# Trigger_Sequencer_Arduino_board.net
KiCad netlist of a schematic drawn in EAGLE
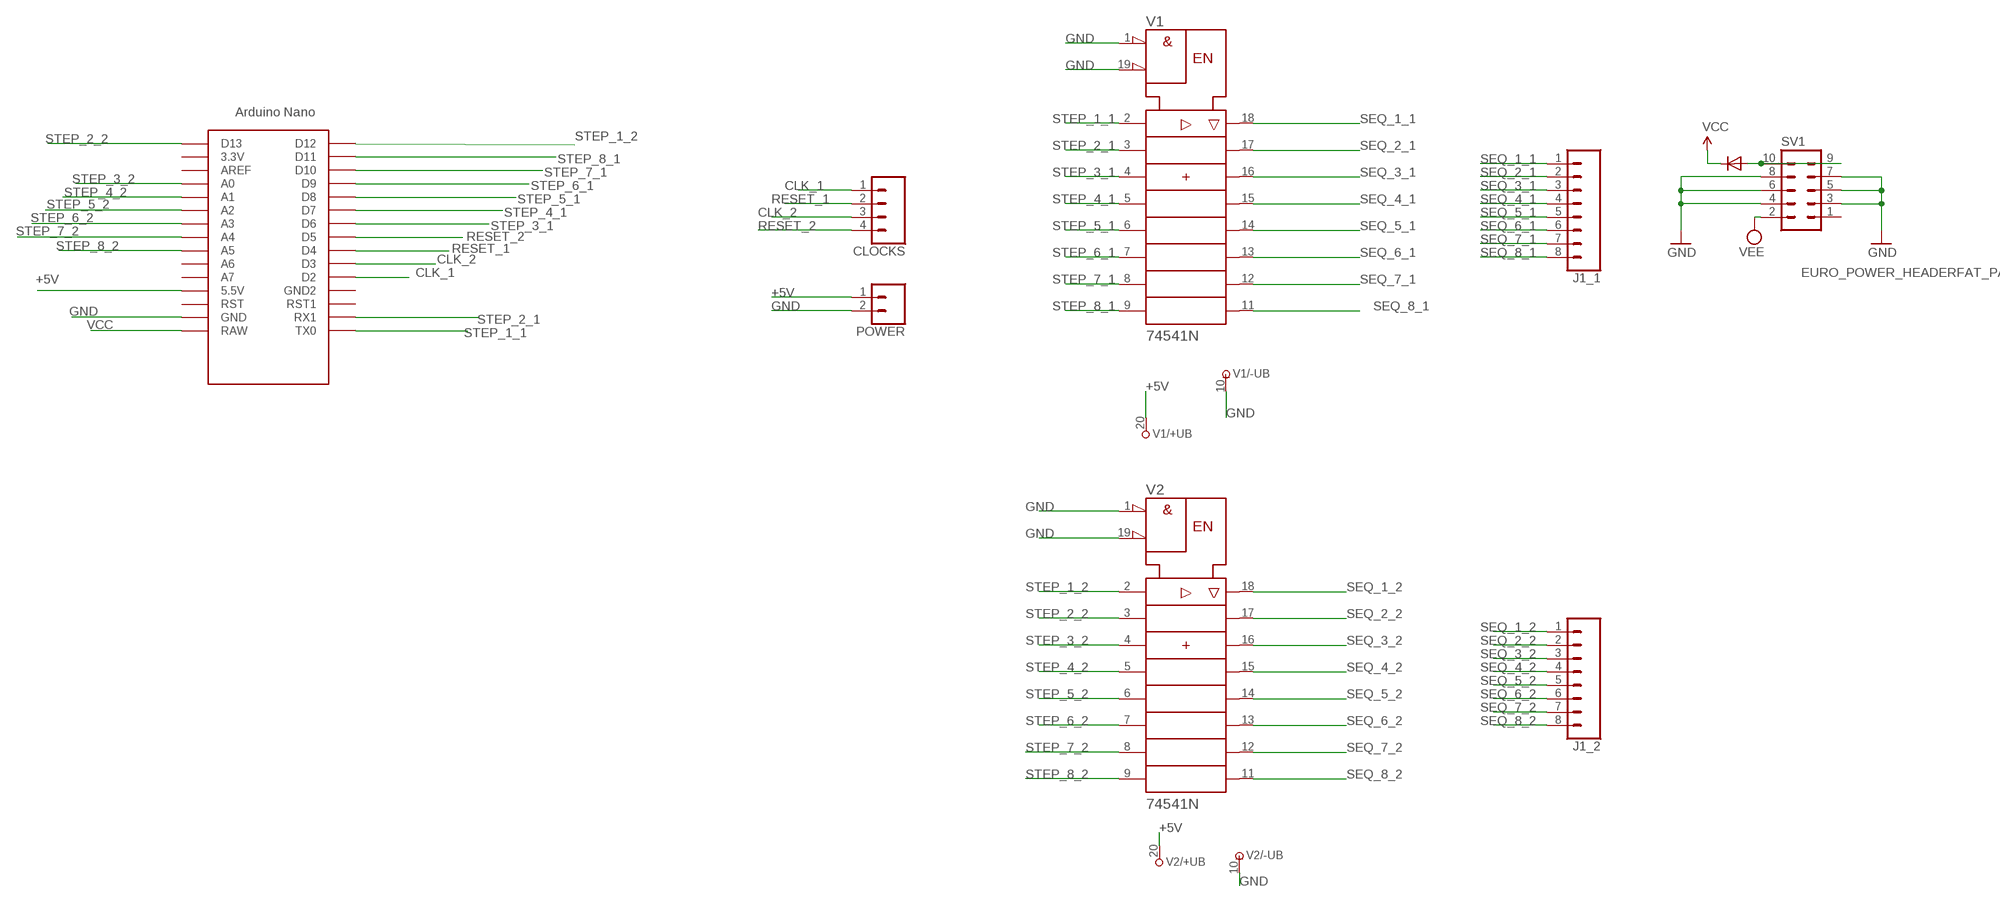
[diagram p0: schematic, sheet 1]

(export (version "E")
  (design (tool "Eeschema 10.0.6"))
  (components
    (comp (ref "CLOCKS")
      (value "CONN_04")
      (footprint "eagle-import:1X04")
      (libsource (lib "eagle-import") (part "CONN_04"))
    )
    (comp (ref "D2")
      (value "1N5819HW")
      (footprint "eagle-import:DO-1N4148")
      (libsource (lib "eagle-import") (part "DIODEDO-1N4148"))
    )
    (comp (ref "J1_1")
      (value "CONN_08NO_SILK_FEMALE_PTH")
      (footprint "eagle-import:1X08_NO_SILK")
      (libsource (lib "eagle-import") (part "CONN_08NO_SILK_FEMALE_PTH"))
    )
    (comp (ref "J1_2")
      (value "CONN_08NO_SILK_FEMALE_PTH")
      (footprint "eagle-import:1X08_NO_SILK")
      (libsource (lib "eagle-import") (part "CONN_08NO_SILK_FEMALE_PTH"))
    )
    (comp (ref "POWER")
      (value "CONN_02")
      (footprint "eagle-import:1X02")
      (libsource (lib "eagle-import") (part "CONN_02"))
    )
    (comp (ref "SV1")
      (value "EURO_POWER_HEADERFAT_PADS")
      (footprint "eagle-import:EURO_PWR_HEADER_FAT")
      (libsource (lib "eagle-import") (part "EURO_POWER_HEADERFAT_PADS"))
    )
    (comp (ref "U$1")
      (value "NANO")
      (footprint "eagle-import:NANO")
      (libsource (lib "eagle-import") (part "NANO"))
    )
    (comp (ref "V1")
      (value "74541N")
      (footprint "eagle-import:DIL20")
      (libsource (lib "eagle-import") (part "74541N"))
    )
    (comp (ref "V2")
      (value "74541N")
      (footprint "eagle-import:DIL20")
      (libsource (lib "eagle-import") (part "74541N"))
    )
  )
  (nets
    (net (code "1") (name "/+5V") (class "Default")
      (node (ref "POWER") (pin "1") (pinfunction "1_1") (pintype "passive"))
      (node (ref "U$1") (pin "5V") (pinfunction "5.5V_5V") (pintype "bidirectional"))
      (node (ref "V1") (pin "20") (pinfunction "+UB_20") (pintype "power_in"))
      (node (ref "V2") (pin "20") (pinfunction "+UB_20") (pintype "power_in"))
    )
    (net (code "2") (name "/CLK_1") (class "Default")
      (node (ref "CLOCKS") (pin "1") (pinfunction "1_1") (pintype "passive"))
      (node (ref "U$1") (pin "D2") (pinfunction "D2_D2") (pintype "bidirectional"))
    )
    (net (code "3") (name "/CLK_2") (class "Default")
      (node (ref "CLOCKS") (pin "3") (pinfunction "3_3") (pintype "passive"))
      (node (ref "U$1") (pin "D3") (pinfunction "D3_D3") (pintype "bidirectional"))
    )
    (net (code "4") (name "/RESET_1") (class "Default")
      (node (ref "CLOCKS") (pin "2") (pinfunction "2_2") (pintype "passive"))
      (node (ref "U$1") (pin "D4") (pinfunction "D4_D4") (pintype "bidirectional"))
    )
    (net (code "5") (name "/RESET_2") (class "Default")
      (node (ref "CLOCKS") (pin "4") (pinfunction "4_4") (pintype "passive"))
      (node (ref "U$1") (pin "D5") (pinfunction "D5_D5") (pintype "bidirectional"))
    )
    (net (code "6") (name "/SEQ_1_1") (class "Default")
      (node (ref "J1_1") (pin "1") (pinfunction "1_1") (pintype "passive"))
      (node (ref "V1") (pin "18") (pinfunction "Y1_18") (pintype "tri_state"))
    )
    (net (code "7") (name "/SEQ_1_2") (class "Default")
      (node (ref "J1_2") (pin "1") (pinfunction "1_1") (pintype "passive"))
      (node (ref "V2") (pin "18") (pinfunction "Y1_18") (pintype "tri_state"))
    )
    (net (code "8") (name "/SEQ_2_1") (class "Default")
      (node (ref "J1_1") (pin "2") (pinfunction "2_2") (pintype "passive"))
      (node (ref "V1") (pin "17") (pinfunction "Y2_17") (pintype "tri_state"))
    )
    (net (code "9") (name "/SEQ_2_2") (class "Default")
      (node (ref "J1_2") (pin "2") (pinfunction "2_2") (pintype "passive"))
      (node (ref "V2") (pin "17") (pinfunction "Y2_17") (pintype "tri_state"))
    )
    (net (code "10") (name "/SEQ_3_1") (class "Default")
      (node (ref "J1_1") (pin "3") (pinfunction "3_3") (pintype "passive"))
      (node (ref "V1") (pin "16") (pinfunction "Y3_16") (pintype "tri_state"))
    )
    (net (code "11") (name "/SEQ_3_2") (class "Default")
      (node (ref "J1_2") (pin "3") (pinfunction "3_3") (pintype "passive"))
      (node (ref "V2") (pin "16") (pinfunction "Y3_16") (pintype "tri_state"))
    )
    (net (code "12") (name "/SEQ_4_1") (class "Default")
      (node (ref "J1_1") (pin "4") (pinfunction "4_4") (pintype "passive"))
      (node (ref "V1") (pin "15") (pinfunction "Y4_15") (pintype "tri_state"))
    )
    (net (code "13") (name "/SEQ_4_2") (class "Default")
      (node (ref "J1_2") (pin "4") (pinfunction "4_4") (pintype "passive"))
      (node (ref "V2") (pin "15") (pinfunction "Y4_15") (pintype "tri_state"))
    )
    (net (code "14") (name "/SEQ_5_1") (class "Default")
      (node (ref "J1_1") (pin "5") (pinfunction "5_5") (pintype "passive"))
      (node (ref "V1") (pin "14") (pinfunction "Y5_14") (pintype "tri_state"))
    )
    (net (code "15") (name "/SEQ_5_2") (class "Default")
      (node (ref "J1_2") (pin "5") (pinfunction "5_5") (pintype "passive"))
      (node (ref "V2") (pin "14") (pinfunction "Y5_14") (pintype "tri_state"))
    )
    (net (code "16") (name "/SEQ_6_1") (class "Default")
      (node (ref "J1_1") (pin "6") (pinfunction "6_6") (pintype "passive"))
      (node (ref "V1") (pin "13") (pinfunction "Y6_13") (pintype "tri_state"))
    )
    (net (code "17") (name "/SEQ_6_2") (class "Default")
      (node (ref "J1_2") (pin "6") (pinfunction "6_6") (pintype "passive"))
      (node (ref "V2") (pin "13") (pinfunction "Y6_13") (pintype "tri_state"))
    )
    (net (code "18") (name "/SEQ_7_1") (class "Default")
      (node (ref "J1_1") (pin "7") (pinfunction "7_7") (pintype "passive"))
      (node (ref "V1") (pin "12") (pinfunction "Y7_12") (pintype "tri_state"))
    )
    (net (code "19") (name "/SEQ_7_2") (class "Default")
      (node (ref "J1_2") (pin "7") (pinfunction "7_7") (pintype "passive"))
      (node (ref "V2") (pin "12") (pinfunction "Y7_12") (pintype "tri_state"))
    )
    (net (code "20") (name "/SEQ_8_1") (class "Default")
      (node (ref "J1_1") (pin "8") (pinfunction "8_8") (pintype "passive"))
      (node (ref "V1") (pin "11") (pinfunction "Y8_11") (pintype "tri_state"))
    )
    (net (code "21") (name "/SEQ_8_2") (class "Default")
      (node (ref "J1_2") (pin "8") (pinfunction "8_8") (pintype "passive"))
      (node (ref "V2") (pin "11") (pinfunction "Y8_11") (pintype "tri_state"))
    )
    (net (code "22") (name "/STEP_1_1") (class "Default")
      (node (ref "U$1") (pin "TX0") (pinfunction "TX0_TX0") (pintype "bidirectional"))
      (node (ref "V1") (pin "2") (pinfunction "A1_2") (pintype "input"))
    )
    (net (code "23") (name "/STEP_1_2") (class "Default")
      (node (ref "U$1") (pin "D12") (pinfunction "D12_D12") (pintype "bidirectional"))
      (node (ref "V2") (pin "2") (pinfunction "A1_2") (pintype "input"))
    )
    (net (code "24") (name "/STEP_2_1") (class "Default")
      (node (ref "U$1") (pin "RX1") (pinfunction "RX1_RX1") (pintype "bidirectional"))
      (node (ref "V1") (pin "3") (pinfunction "A2_3") (pintype "input"))
    )
    (net (code "25") (name "/STEP_2_2") (class "Default")
      (node (ref "U$1") (pin "D13") (pinfunction "D13_D13") (pintype "bidirectional"))
      (node (ref "V2") (pin "3") (pinfunction "A2_3") (pintype "input"))
    )
    (net (code "26") (name "/STEP_3_1") (class "Default")
      (node (ref "U$1") (pin "D6") (pinfunction "D6_D6") (pintype "bidirectional"))
      (node (ref "V1") (pin "4") (pinfunction "A3_4") (pintype "input"))
    )
    (net (code "27") (name "/STEP_3_2") (class "Default")
      (node (ref "U$1") (pin "A0") (pinfunction "A0_A0") (pintype "bidirectional"))
      (node (ref "V2") (pin "4") (pinfunction "A3_4") (pintype "input"))
    )
    (net (code "28") (name "/STEP_4_1") (class "Default")
      (node (ref "U$1") (pin "D7") (pinfunction "D7_D7") (pintype "bidirectional"))
      (node (ref "V1") (pin "5") (pinfunction "A4_5") (pintype "input"))
    )
    (net (code "29") (name "/STEP_4_2") (class "Default")
      (node (ref "U$1") (pin "A1") (pinfunction "A1_A1") (pintype "bidirectional"))
      (node (ref "V2") (pin "5") (pinfunction "A4_5") (pintype "input"))
    )
    (net (code "30") (name "/STEP_5_1") (class "Default")
      (node (ref "U$1") (pin "D8") (pinfunction "D8_D8") (pintype "bidirectional"))
      (node (ref "V1") (pin "6") (pinfunction "A5_6") (pintype "input"))
    )
    (net (code "31") (name "/STEP_5_2") (class "Default")
      (node (ref "U$1") (pin "A2") (pinfunction "A2_A2") (pintype "bidirectional"))
      (node (ref "V2") (pin "6") (pinfunction "A5_6") (pintype "input"))
    )
    (net (code "32") (name "/STEP_6_1") (class "Default")
      (node (ref "U$1") (pin "D9") (pinfunction "D9_D9") (pintype "bidirectional"))
      (node (ref "V1") (pin "7") (pinfunction "A6_7") (pintype "input"))
    )
    (net (code "33") (name "/STEP_6_2") (class "Default")
      (node (ref "U$1") (pin "A3") (pinfunction "A3_A3") (pintype "bidirectional"))
      (node (ref "V2") (pin "7") (pinfunction "A6_7") (pintype "input"))
    )
    (net (code "34") (name "/STEP_7_1") (class "Default")
      (node (ref "U$1") (pin "D10") (pinfunction "D10_D10") (pintype "bidirectional"))
      (node (ref "V1") (pin "8") (pinfunction "A7_8") (pintype "input"))
    )
    (net (code "35") (name "/STEP_7_2") (class "Default")
      (node (ref "U$1") (pin "A4") (pinfunction "A4_A4") (pintype "bidirectional"))
      (node (ref "V2") (pin "8") (pinfunction "A7_8") (pintype "input"))
    )
    (net (code "36") (name "/STEP_8_1") (class "Default")
      (node (ref "U$1") (pin "D11") (pinfunction "D11_D11") (pintype "bidirectional"))
      (node (ref "V1") (pin "9") (pinfunction "A8_9") (pintype "input"))
    )
    (net (code "37") (name "/STEP_8_2") (class "Default")
      (node (ref "U$1") (pin "A5") (pinfunction "A5_A5") (pintype "bidirectional"))
      (node (ref "V2") (pin "9") (pinfunction "A8_9") (pintype "input"))
    )
    (net (code "38") (name "GND") (class "Default")
      (node (ref "POWER") (pin "2") (pinfunction "2_2") (pintype "passive"))
      (node (ref "SV1") (pin "3") (pinfunction "3_3") (pintype "passive"))
      (node (ref "SV1") (pin "4") (pinfunction "4_4") (pintype "passive"))
      (node (ref "SV1") (pin "5") (pinfunction "5_5") (pintype "passive"))
      (node (ref "SV1") (pin "6") (pinfunction "6_6") (pintype "passive"))
      (node (ref "SV1") (pin "7") (pinfunction "7_7") (pintype "passive"))
      (node (ref "SV1") (pin "8") (pinfunction "8_8") (pintype "passive"))
      (node (ref "U$1") (pin "GND") (pinfunction "GND_GND") (pintype "bidirectional"))
      (node (ref "V1") (pin "1") (pinfunction "~{G1}_1") (pintype "input"))
      (node (ref "V1") (pin "10") (pinfunction "-UB_10") (pintype "power_in"))
      (node (ref "V1") (pin "19") (pinfunction "~{G2}_19") (pintype "input"))
      (node (ref "V2") (pin "1") (pinfunction "~{G1}_1") (pintype "input"))
      (node (ref "V2") (pin "10") (pinfunction "-UB_10") (pintype "power_in"))
      (node (ref "V2") (pin "19") (pinfunction "~{G2}_19") (pintype "input"))
    )
    (net (code "39") (name "Net-(D2-PadA)") (class "Default")
      (node (ref "D2") (pin "A") (pinfunction "A_A") (pintype "passive"))
      (node (ref "SV1") (pin "10") (pinfunction "10_10") (pintype "passive"))
      (node (ref "SV1") (pin "9") (pinfunction "9_9") (pintype "passive"))
    )
    (net (code "40") (name "VCC") (class "Default")
      (node (ref "D2") (pin "C") (pinfunction "C_C") (pintype "passive"))
      (node (ref "U$1") (pin "RAW") (pinfunction "RAW_RAW") (pintype "bidirectional"))
    )
    (net (code "41") (name "VEE") (class "Default")
      (node (ref "SV1") (pin "2") (pinfunction "2_2") (pintype "passive"))
    )
    (net (code "42") (name "unconnected-(SV1-Pad1)") (class "Default")
      (node (ref "SV1") (pin "1") (pinfunction "1_1") (pintype "passive"))
    )
    (net (code "43") (name "unconnected-(U$1-GND2-PadGND1)") (class "Default")
      (node (ref "U$1") (pin "GND1") (pinfunction "GND2_GND1") (pintype "bidirectional"))
    )
    (net (code "44") (name "unconnected-(U$1-Pad3.3V)") (class "Default")
      (node (ref "U$1") (pin "3.3V") (pinfunction "3.3V_3.3V") (pintype "bidirectional"))
    )
    (net (code "45") (name "unconnected-(U$1-PadA6)") (class "Default")
      (node (ref "U$1") (pin "A6") (pinfunction "A6_A6") (pintype "bidirectional"))
    )
    (net (code "46") (name "unconnected-(U$1-PadA7)") (class "Default")
      (node (ref "U$1") (pin "A7") (pinfunction "A7_A7") (pintype "bidirectional"))
    )
    (net (code "47") (name "unconnected-(U$1-PadAREF)") (class "Default")
      (node (ref "U$1") (pin "AREF") (pinfunction "AREF_AREF") (pintype "bidirectional"))
    )
    (net (code "48") (name "unconnected-(U$1-PadRST)") (class "Default")
      (node (ref "U$1") (pin "RST") (pinfunction "RST_RST") (pintype "bidirectional"))
    )
    (net (code "49") (name "unconnected-(U$1-PadRST1)") (class "Default")
      (node (ref "U$1") (pin "RST1") (pinfunction "RST1_RST1") (pintype "bidirectional"))
    )
  )
)
